# WR_LINK.net
KiCad netlist of a schematic drawn in Altium Designer
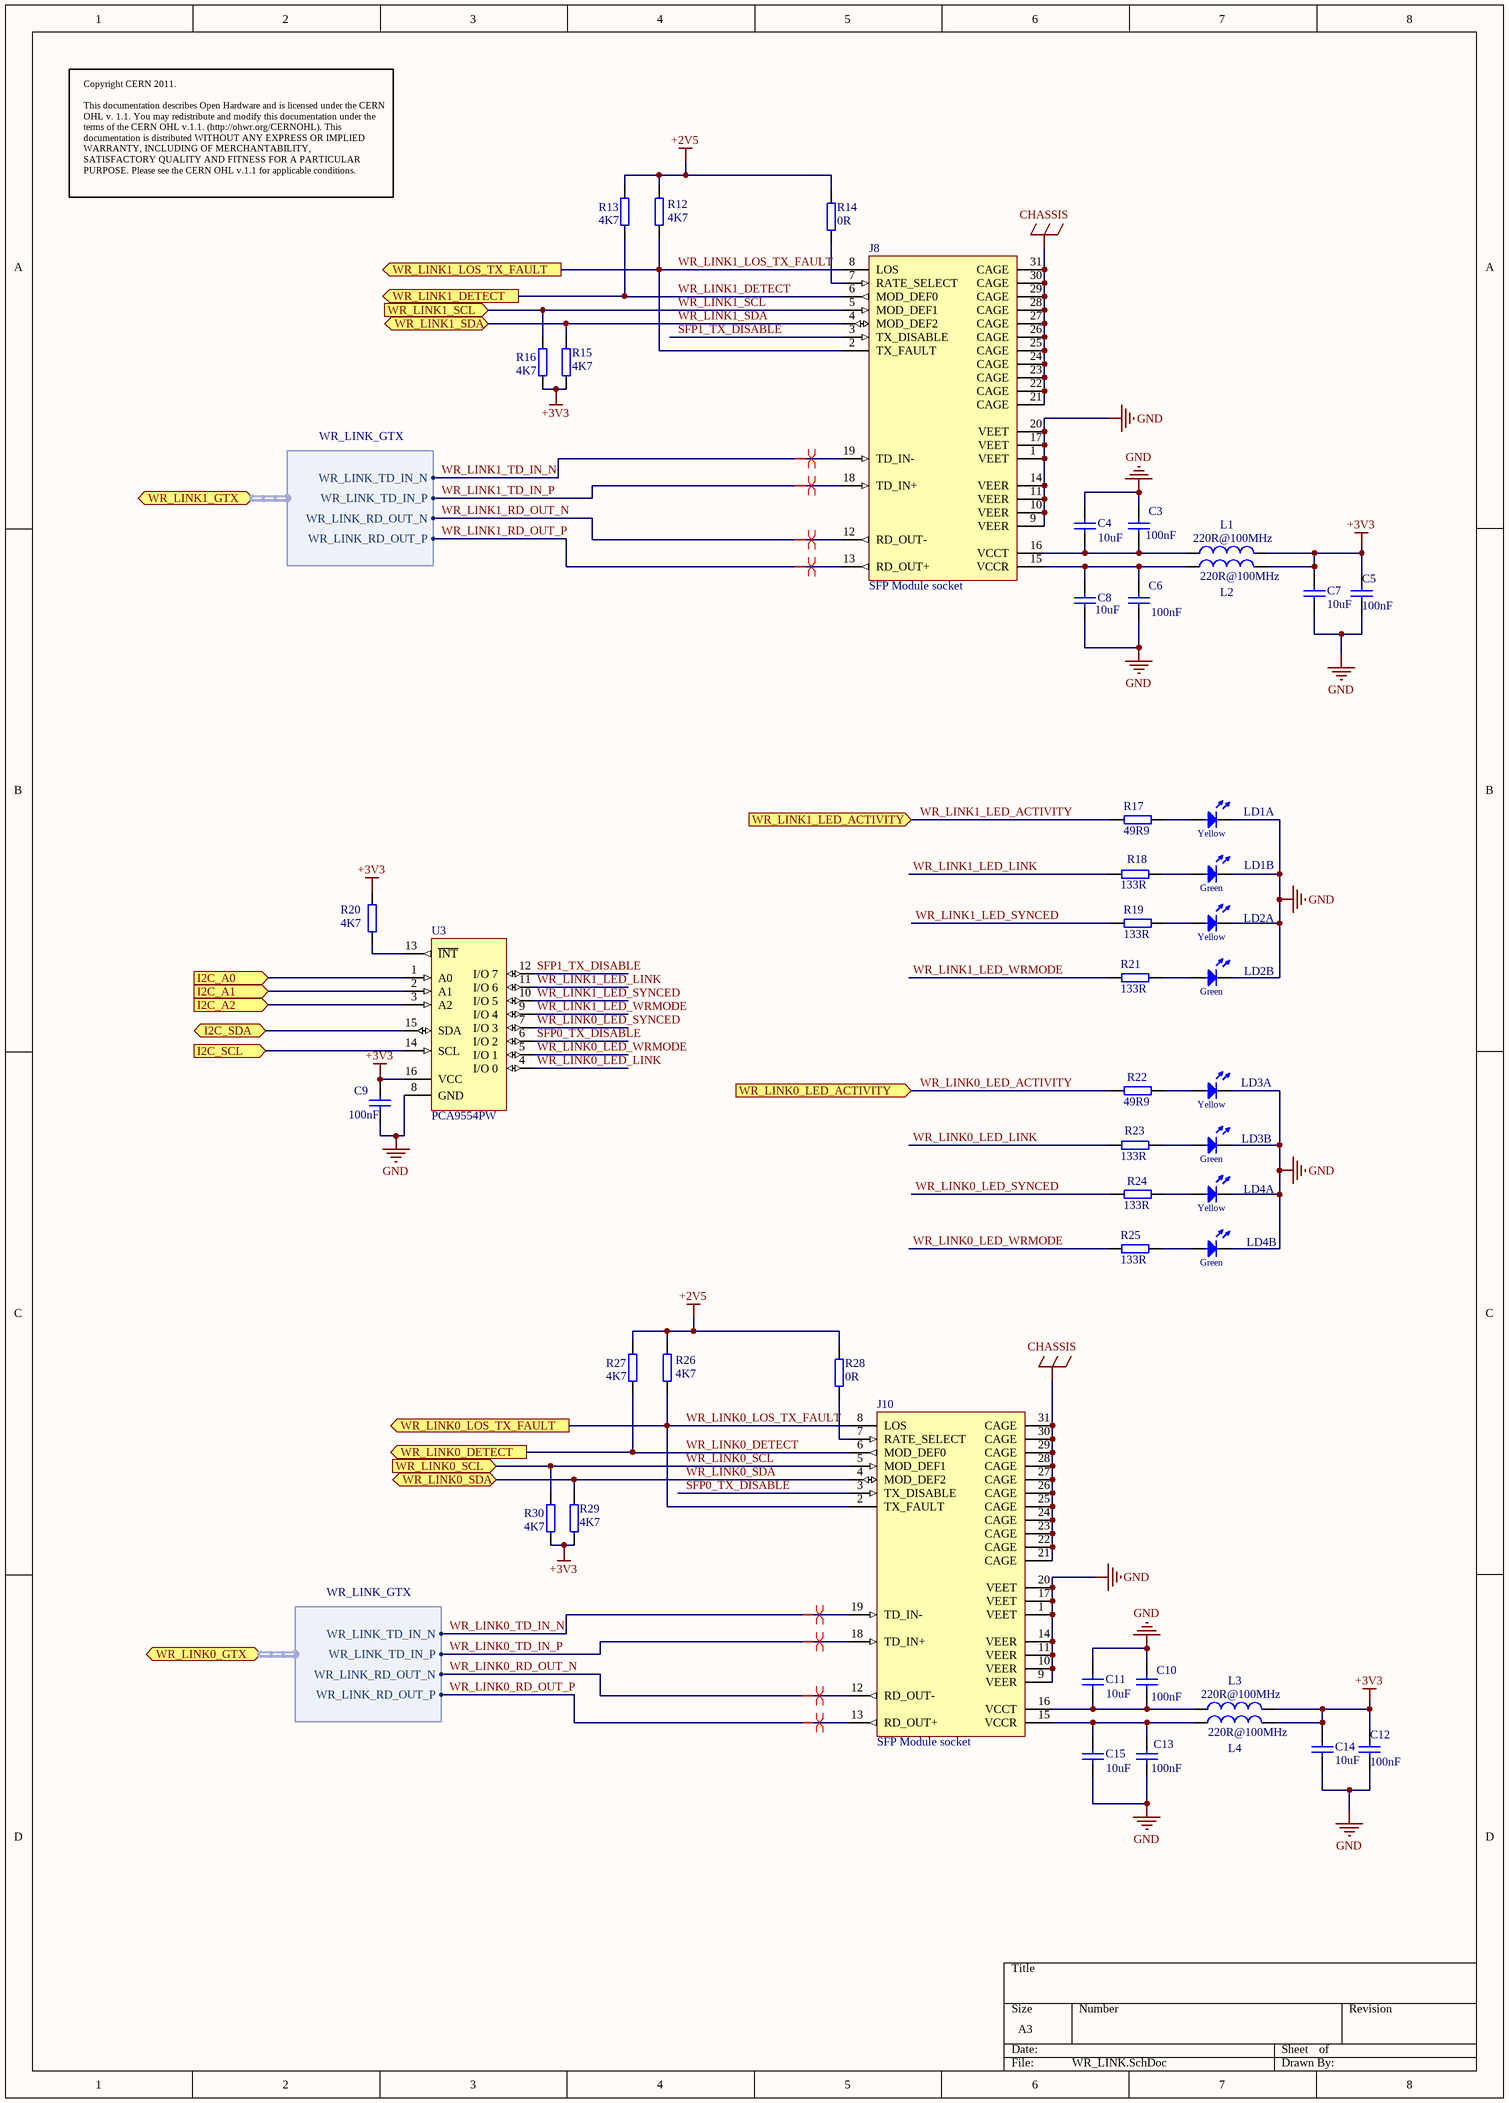
[diagram p0: WR_LINK.SchDoc]

(export (version "E")
  (design (tool "Eeschema 10.0.6"))
  (components
    (comp (ref "C3")
      (value "100nF")
      (footprint "CC1608-0603")
      (description "Capacitor")
      (fields
        (field (name "TOLERANCE") "±10%")
        (field (name "VOLTAGE") "16V")
        (field (name "PUBLISHER") "Altium Limited")
      )
      (libsource (lib "wr_switch") (part "Cap"))
    )
    (comp (ref "C4")
      (value "10uF")
      (footprint "CC2012-0805")
      (description "Capacitor")
      (fields
        (field (name "TOLERANCE") "±10%")
        (field (name "VOLTAGE") "16V")
        (field (name "PUBLISHER") "Altium Limited")
      )
      (libsource (lib "wr_switch") (part "Cap"))
    )
    (comp (ref "C5")
      (value "100nF")
      (footprint "CC1608-0603")
      (description "Capacitor")
      (fields
        (field (name "TOLERANCE") "±10%")
        (field (name "VOLTAGE") "16V")
        (field (name "PUBLISHER") "Altium Limited")
      )
      (libsource (lib "wr_switch") (part "Cap"))
    )
    (comp (ref "C6")
      (value "100nF")
      (footprint "CC1608-0603")
      (description "Capacitor")
      (fields
        (field (name "TOLERANCE") "±10%")
        (field (name "VOLTAGE") "16V")
        (field (name "PUBLISHER") "Altium Limited")
      )
      (libsource (lib "wr_switch") (part "Cap"))
    )
    (comp (ref "C7")
      (value "10uF")
      (footprint "CC1608-0603")
      (description "Capacitor")
      (fields
        (field (name "TOLERANCE") "±20%")
        (field (name "VOLTAGE") "6.3V")
        (field (name "PUBLISHER") "Altium Limited")
      )
      (libsource (lib "wr_switch") (part "Cap"))
    )
    (comp (ref "C8")
      (value "10uF")
      (footprint "CC2012-0805")
      (description "Capacitor")
      (fields
        (field (name "TOLERANCE") "±10%")
        (field (name "VOLTAGE") "16V")
        (field (name "PUBLISHER") "Altium Limited")
      )
      (libsource (lib "wr_switch") (part "Cap"))
    )
    (comp (ref "C9")
      (value "100nF")
      (footprint "CC1608-0603")
      (description "Capacitor")
      (fields
        (field (name "TOLERANCE") "±10%")
        (field (name "VOLTAGE") "16V")
        (field (name "PUBLISHER") "Altium Limited")
      )
      (libsource (lib "wr_switch") (part "Cap"))
    )
    (comp (ref "C10")
      (value "100nF")
      (footprint "CC1608-0603")
      (description "Capacitor")
      (fields
        (field (name "TOLERANCE") "±10%")
        (field (name "VOLTAGE") "16V")
        (field (name "PUBLISHER") "Altium Limited")
      )
      (libsource (lib "wr_switch") (part "Cap"))
    )
    (comp (ref "C11")
      (value "10uF")
      (footprint "CC2012-0805")
      (description "Capacitor")
      (fields
        (field (name "TOLERANCE") "±10%")
        (field (name "VOLTAGE") "16V")
        (field (name "PUBLISHER") "Altium Limited")
      )
      (libsource (lib "wr_switch") (part "Cap"))
    )
    (comp (ref "C12")
      (value "100nF")
      (footprint "CC1608-0603")
      (description "Capacitor")
      (fields
        (field (name "TOLERANCE") "±10%")
        (field (name "VOLTAGE") "16V")
        (field (name "PUBLISHER") "Altium Limited")
      )
      (libsource (lib "wr_switch") (part "Cap"))
    )
    (comp (ref "C13")
      (value "100nF")
      (footprint "CC1608-0603")
      (description "Capacitor")
      (fields
        (field (name "TOLERANCE") "±10%")
        (field (name "VOLTAGE") "16V")
        (field (name "PUBLISHER") "Altium Limited")
      )
      (libsource (lib "wr_switch") (part "Cap"))
    )
    (comp (ref "C14")
      (value "10uF")
      (footprint "CC1608-0603")
      (description "Capacitor")
      (fields
        (field (name "TOLERANCE") "±20%")
        (field (name "VOLTAGE") "6.3V")
        (field (name "PUBLISHER") "Altium Limited")
      )
      (libsource (lib "wr_switch") (part "Cap"))
    )
    (comp (ref "C15")
      (value "10uF")
      (footprint "CC2012-0805")
      (description "Capacitor")
      (fields
        (field (name "TOLERANCE") "±10%")
        (field (name "VOLTAGE") "16V")
        (field (name "PUBLISHER") "Altium Limited")
      )
      (libsource (lib "wr_switch") (part "Cap"))
    )
    (comp (ref "J8")
      (value "SFP Module socket")
      (footprint "7S_WR:SFP_SINGLE_PORT")
      (description "Socket for SFP module")
      (libsource (lib "wr_switch") (part "SFP_SOCKET_SINGLE"))
    )
    (comp (ref "J10")
      (value "SFP Module socket")
      (footprint "7S_WR:SFP_SINGLE_PORT")
      (description "Socket for SFP module")
      (libsource (lib "wr_switch") (part "SFP_SOCKET_SINGLE"))
    )
    (comp (ref "L1")
      (value "220R@100MHz Ferrite Bead")
      (footprint "0603")
      (description "ferrite bead")
      (fields (field (name "IMPEDANCE") "220R@100MHz"))
      (libsource (lib "wr_switch") (part "L_FERRITE_BEAD"))
    )
    (comp (ref "L2")
      (value "220R@100MHz Ferrite Bead")
      (footprint "0603")
      (description "ferrite bead")
      (fields (field (name "IMPEDANCE") "220R@100MHz"))
      (libsource (lib "wr_switch") (part "L_FERRITE_BEAD"))
    )
    (comp (ref "L3")
      (value "220R@100MHz Ferrite Bead")
      (footprint "0603")
      (description "ferrite bead")
      (fields (field (name "IMPEDANCE") "220R@100MHz"))
      (libsource (lib "wr_switch") (part "L_FERRITE_BEAD"))
    )
    (comp (ref "L4")
      (value "220R@100MHz Ferrite Bead")
      (footprint "0603")
      (description "ferrite bead")
      (fields (field (name "IMPEDANCE") "220R@100MHz"))
      (libsource (lib "wr_switch") (part "L_FERRITE_BEAD"))
    )
    (comp (ref "LD1")
      (value "Green/Yellow")
      (footprint "7S_WR:LED_DIALIGHT_591-3x0x-0xx")
      (description "Bi-Color LED SMD")
      (libsource (lib "wr_switch") (part "LED_DIALIGHT_591-3x0x"))
    )
    (comp (ref "LD2")
      (value "Green/Yellow")
      (footprint "7S_WR:LED_DIALIGHT_591-3x0x-0xx")
      (description "Bi-Color LED SMD")
      (libsource (lib "wr_switch") (part "LED_DIALIGHT_591-3x0x"))
    )
    (comp (ref "LD3")
      (value "Green/Yellow")
      (footprint "7S_WR:LED_DIALIGHT_591-3x0x-0xx")
      (description "Bi-Color LED SMD")
      (libsource (lib "wr_switch") (part "LED_DIALIGHT_591-3x0x"))
    )
    (comp (ref "LD4")
      (value "Green/Yellow")
      (footprint "7S_WR:LED_DIALIGHT_591-3x0x-0xx")
      (description "Bi-Color LED SMD")
      (libsource (lib "wr_switch") (part "LED_DIALIGHT_591-3x0x"))
    )
    (comp (ref "R12")
      (value "4K7")
      (footprint "0603")
      (description "SMD Resistor")
      (fields (field (name "TOLERANCE") "±1%"))
      (libsource (lib "wr_switch") (part "RES_SMD"))
    )
    (comp (ref "R13")
      (value "4K7")
      (footprint "0603")
      (description "SMD Resistor")
      (fields (field (name "TOLERANCE") "±1%"))
      (libsource (lib "wr_switch") (part "RES_SMD"))
    )
    (comp (ref "R14")
      (value "0R")
      (footprint "0603")
      (description "SMD Resistor")
      (libsource (lib "wr_switch") (part "RES_SMD"))
    )
    (comp (ref "R15")
      (value "4K7")
      (footprint "0603")
      (description "SMD Resistor")
      (fields (field (name "TOLERANCE") "±1%"))
      (libsource (lib "wr_switch") (part "RES_SMD"))
    )
    (comp (ref "R16")
      (value "4K7")
      (footprint "0603")
      (description "SMD Resistor")
      (fields (field (name "TOLERANCE") "±1%"))
      (libsource (lib "wr_switch") (part "RES_SMD"))
    )
    (comp (ref "R17")
      (value "49R9")
      (footprint "0603")
      (description "SMD Resistor")
      (fields (field (name "TOLERANCE") "±1%"))
      (libsource (lib "wr_switch") (part "RES_SMD"))
    )
    (comp (ref "R18")
      (value "133R")
      (footprint "0603")
      (description "SMD Resistor")
      (fields (field (name "TOLERANCE") "±1%"))
      (libsource (lib "wr_switch") (part "RES_SMD"))
    )
    (comp (ref "R19")
      (value "133R")
      (footprint "0603")
      (description "SMD Resistor")
      (fields (field (name "TOLERANCE") "±1%"))
      (libsource (lib "wr_switch") (part "RES_SMD"))
    )
    (comp (ref "R20")
      (value "4K7")
      (footprint "0603")
      (description "SMD Resistor")
      (fields (field (name "TOLERANCE") "±1%"))
      (libsource (lib "wr_switch") (part "RES_SMD"))
    )
    (comp (ref "R21")
      (value "133R")
      (footprint "0603")
      (description "SMD Resistor")
      (fields (field (name "TOLERANCE") "±1%"))
      (libsource (lib "wr_switch") (part "RES_SMD"))
    )
    (comp (ref "R22")
      (value "49R9")
      (footprint "0603")
      (description "SMD Resistor")
      (fields (field (name "TOLERANCE") "±1%"))
      (libsource (lib "wr_switch") (part "RES_SMD"))
    )
    (comp (ref "R23")
      (value "133R")
      (footprint "0603")
      (description "SMD Resistor")
      (fields (field (name "TOLERANCE") "±1%"))
      (libsource (lib "wr_switch") (part "RES_SMD"))
    )
    (comp (ref "R24")
      (value "133R")
      (footprint "0603")
      (description "SMD Resistor")
      (fields (field (name "TOLERANCE") "±1%"))
      (libsource (lib "wr_switch") (part "RES_SMD"))
    )
    (comp (ref "R25")
      (value "133R")
      (footprint "0603")
      (description "SMD Resistor")
      (fields (field (name "TOLERANCE") "±1%"))
      (libsource (lib "wr_switch") (part "RES_SMD"))
    )
    (comp (ref "R26")
      (value "4K7")
      (footprint "0603")
      (description "SMD Resistor")
      (fields (field (name "TOLERANCE") "±1%"))
      (libsource (lib "wr_switch") (part "RES_SMD"))
    )
    (comp (ref "R27")
      (value "4K7")
      (footprint "0603")
      (description "SMD Resistor")
      (fields (field (name "TOLERANCE") "±1%"))
      (libsource (lib "wr_switch") (part "RES_SMD"))
    )
    (comp (ref "R28")
      (value "0R")
      (footprint "0603")
      (description "SMD Resistor")
      (libsource (lib "wr_switch") (part "RES_SMD"))
    )
    (comp (ref "R29")
      (value "4K7")
      (footprint "0603")
      (description "SMD Resistor")
      (fields (field (name "TOLERANCE") "±1%"))
      (libsource (lib "wr_switch") (part "RES_SMD"))
    )
    (comp (ref "R30")
      (value "4K7")
      (footprint "0603")
      (description "SMD Resistor")
      (fields (field (name "TOLERANCE") "±1%"))
      (libsource (lib "wr_switch") (part "RES_SMD"))
    )
    (comp (ref "U3")
      (value "PCA9554PW")
      (footprint "SOP65P640X120-16N")
      (description "8-bit I2C-bus SMBus I/O port with interrupt")
      (libsource (lib "wr_switch") (part "PCA9554D"))
    )
  )
  (nets
    (net (code "2") (name "+2V5") (class "Default")
      (node (ref "R12") (pin "2") (pinfunction "2_2") (pintype "passive"))
      (node (ref "R13") (pin "2") (pinfunction "2_2") (pintype "passive"))
      (node (ref "R14") (pin "1") (pinfunction "1_1") (pintype "passive"))
      (node (ref "R26") (pin "2") (pinfunction "2_2") (pintype "passive"))
      (node (ref "R27") (pin "2") (pinfunction "2_2") (pintype "passive"))
      (node (ref "R28") (pin "1") (pinfunction "1_1") (pintype "passive"))
    )
    (net (code "3") (name "+3V3") (class "Default")
      (node (ref "C12") (pin "1") (pinfunction "1_1") (pintype "passive"))
      (node (ref "C14") (pin "1") (pinfunction "1_1") (pintype "passive"))
      (node (ref "C5") (pin "1") (pinfunction "1_1") (pintype "passive"))
      (node (ref "C7") (pin "1") (pinfunction "1_1") (pintype "passive"))
      (node (ref "C9") (pin "1") (pinfunction "1_1") (pintype "passive"))
      (node (ref "L1") (pin "2") (pinfunction "2_2") (pintype "passive"))
      (node (ref "L2") (pin "2") (pinfunction "2_2") (pintype "passive"))
      (node (ref "L3") (pin "2") (pinfunction "2_2") (pintype "passive"))
      (node (ref "L4") (pin "2") (pinfunction "2_2") (pintype "passive"))
      (node (ref "R15") (pin "2") (pinfunction "2_2") (pintype "passive"))
      (node (ref "R16") (pin "2") (pinfunction "2_2") (pintype "passive"))
      (node (ref "R20") (pin "2") (pinfunction "2_2") (pintype "passive"))
      (node (ref "R29") (pin "2") (pinfunction "2_2") (pintype "passive"))
      (node (ref "R30") (pin "2") (pinfunction "2_2") (pintype "passive"))
      (node (ref "U3") (pin "16") (pinfunction "VCC_16") (pintype "power_in"))
    )
    (net (code "4") (name "/I2C_A0") (class "Default")
      (node (ref "U3") (pin "1") (pinfunction "A0_1") (pintype "input"))
    )
    (net (code "5") (name "/I2C_A1") (class "Default")
      (node (ref "U3") (pin "2") (pinfunction "A1_2") (pintype "input"))
    )
    (net (code "6") (name "/I2C_A2") (class "Default")
      (node (ref "U3") (pin "3") (pinfunction "A2_3") (pintype "input"))
    )
    (net (code "7") (name "/I2C_SCL") (class "Default")
      (node (ref "U3") (pin "14") (pinfunction "SCL_14") (pintype "input"))
    )
    (net (code "8") (name "/I2C_SDA") (class "Default")
      (node (ref "U3") (pin "15") (pinfunction "SDA_15") (pintype "bidirectional"))
    )
    (net (code "9") (name "/SFP0_TX_DISABLE") (class "Default")
      (node (ref "J10") (pin "3") (pinfunction "TX_DISABLE_3") (pintype "input"))
      (node (ref "U3") (pin "6") (pinfunction "I/O_2_6") (pintype "bidirectional"))
    )
    (net (code "10") (name "/SFP1_TX_DISABLE") (class "Default")
      (node (ref "J8") (pin "3") (pinfunction "TX_DISABLE_3") (pintype "input"))
      (node (ref "U3") (pin "12") (pinfunction "I/O_7_12") (pintype "bidirectional"))
    )
    (net (code "11") (name "/WR_LINK0_DETECT") (class "Default")
      (node (ref "J10") (pin "6") (pinfunction "MOD_DEF0_6") (pintype "output"))
      (node (ref "R27") (pin "1") (pinfunction "1_1") (pintype "passive"))
    )
    (net (code "12") (name "/WR_LINK0_LED_ACTIVITY") (class "Default")
      (node (ref "R22") (pin "1") (pinfunction "1_1") (pintype "passive"))
    )
    (net (code "13") (name "/WR_LINK0_LED_LINK") (class "Default")
      (node (ref "R23") (pin "1") (pinfunction "1_1") (pintype "passive"))
      (node (ref "U3") (pin "4") (pinfunction "I/O_0_4") (pintype "bidirectional"))
    )
    (net (code "14") (name "/WR_LINK0_LED_SYNCED") (class "Default")
      (node (ref "R24") (pin "1") (pinfunction "1_1") (pintype "passive"))
      (node (ref "U3") (pin "7") (pinfunction "I/O_3_7") (pintype "bidirectional"))
    )
    (net (code "15") (name "/WR_LINK0_LED_WRMODE") (class "Default")
      (node (ref "R25") (pin "1") (pinfunction "1_1") (pintype "passive"))
      (node (ref "U3") (pin "5") (pinfunction "I/O_1_5") (pintype "bidirectional"))
    )
    (net (code "16") (name "/WR_LINK0_LOS_TX_FAULT") (class "Default")
      (node (ref "J10") (pin "2") (pinfunction "TX_FAULT_2") (pintype "open_collector"))
      (node (ref "J10") (pin "8") (pinfunction "LOS_8") (pintype "open_collector"))
      (node (ref "R26") (pin "1") (pinfunction "1_1") (pintype "passive"))
    )
    (net (code "17") (name "/WR_LINK0_RD_OUT_N") (class "Default")
      (node (ref "J10") (pin "12") (pinfunction "RD_OUT-_12") (pintype "output"))
    )
    (net (code "18") (name "/WR_LINK0_RD_OUT_P") (class "Default")
      (node (ref "J10") (pin "13") (pinfunction "RD_OUT+_13") (pintype "output"))
    )
    (net (code "19") (name "/WR_LINK0_SCL") (class "Default")
      (node (ref "J10") (pin "5") (pinfunction "MOD_DEF1_5") (pintype "input"))
      (node (ref "R30") (pin "1") (pinfunction "1_1") (pintype "passive"))
    )
    (net (code "20") (name "/WR_LINK0_SDA") (class "Default")
      (node (ref "J10") (pin "4") (pinfunction "MOD_DEF2_4") (pintype "bidirectional"))
      (node (ref "R29") (pin "1") (pinfunction "1_1") (pintype "passive"))
    )
    (net (code "21") (name "/WR_LINK0_TD_IN_N") (class "Default")
      (node (ref "J10") (pin "19") (pinfunction "TD_IN-_19") (pintype "input"))
    )
    (net (code "22") (name "/WR_LINK0_TD_IN_P") (class "Default")
      (node (ref "J10") (pin "18") (pinfunction "TD_IN+_18") (pintype "input"))
    )
    (net (code "23") (name "/WR_LINK1_DETECT") (class "Default")
      (node (ref "J8") (pin "6") (pinfunction "MOD_DEF0_6") (pintype "output"))
      (node (ref "R13") (pin "1") (pinfunction "1_1") (pintype "passive"))
    )
    (net (code "24") (name "/WR_LINK1_LED_ACTIVITY") (class "Default")
      (node (ref "R17") (pin "1") (pinfunction "1_1") (pintype "passive"))
    )
    (net (code "25") (name "/WR_LINK1_LED_LINK") (class "Default")
      (node (ref "R18") (pin "1") (pinfunction "1_1") (pintype "passive"))
      (node (ref "U3") (pin "11") (pinfunction "I/O_6_11") (pintype "bidirectional"))
    )
    (net (code "26") (name "/WR_LINK1_LED_SYNCED") (class "Default")
      (node (ref "R19") (pin "1") (pinfunction "1_1") (pintype "passive"))
      (node (ref "U3") (pin "10") (pinfunction "I/O_5_10") (pintype "bidirectional"))
    )
    (net (code "27") (name "/WR_LINK1_LED_WRMODE") (class "Default")
      (node (ref "R21") (pin "1") (pinfunction "1_1") (pintype "passive"))
      (node (ref "U3") (pin "9") (pinfunction "I/O_4_9") (pintype "bidirectional"))
    )
    (net (code "28") (name "/WR_LINK1_LOS_TX_FAULT") (class "Default")
      (node (ref "J8") (pin "2") (pinfunction "TX_FAULT_2") (pintype "open_collector"))
      (node (ref "J8") (pin "8") (pinfunction "LOS_8") (pintype "open_collector"))
      (node (ref "R12") (pin "1") (pinfunction "1_1") (pintype "passive"))
    )
    (net (code "29") (name "/WR_LINK1_RD_OUT_N") (class "Default")
      (node (ref "J8") (pin "12") (pinfunction "RD_OUT-_12") (pintype "output"))
    )
    (net (code "30") (name "/WR_LINK1_RD_OUT_P") (class "Default")
      (node (ref "J8") (pin "13") (pinfunction "RD_OUT+_13") (pintype "output"))
    )
    (net (code "31") (name "/WR_LINK1_SCL") (class "Default")
      (node (ref "J8") (pin "5") (pinfunction "MOD_DEF1_5") (pintype "input"))
      (node (ref "R16") (pin "1") (pinfunction "1_1") (pintype "passive"))
    )
    (net (code "32") (name "/WR_LINK1_SDA") (class "Default")
      (node (ref "J8") (pin "4") (pinfunction "MOD_DEF2_4") (pintype "bidirectional"))
      (node (ref "R15") (pin "1") (pinfunction "1_1") (pintype "passive"))
    )
    (net (code "33") (name "/WR_LINK1_TD_IN_N") (class "Default")
      (node (ref "J8") (pin "19") (pinfunction "TD_IN-_19") (pintype "input"))
    )
    (net (code "34") (name "/WR_LINK1_TD_IN_P") (class "Default")
      (node (ref "J8") (pin "18") (pinfunction "TD_IN+_18") (pintype "input"))
    )
    (net (code "36") (name "CHASSIS") (class "Default")
      (node (ref "J10") (pin "21") (pinfunction "CAGE_21") (pintype "power_in"))
      (node (ref "J10") (pin "22") (pinfunction "CAGE_22") (pintype "power_in"))
      (node (ref "J10") (pin "23") (pinfunction "CAGE_23") (pintype "power_in"))
      (node (ref "J10") (pin "24") (pinfunction "CAGE_24") (pintype "power_in"))
      (node (ref "J10") (pin "25") (pinfunction "CAGE_25") (pintype "power_in"))
      (node (ref "J10") (pin "26") (pinfunction "CAGE_26") (pintype "power_in"))
      (node (ref "J10") (pin "27") (pinfunction "CAGE_27") (pintype "power_in"))
      (node (ref "J10") (pin "28") (pinfunction "CAGE_28") (pintype "power_in"))
      (node (ref "J10") (pin "29") (pinfunction "CAGE_29") (pintype "power_in"))
      (node (ref "J10") (pin "30") (pinfunction "CAGE_30") (pintype "power_in"))
      (node (ref "J10") (pin "31") (pinfunction "CAGE_31") (pintype "power_in"))
      (node (ref "J8") (pin "21") (pinfunction "CAGE_21") (pintype "power_in"))
      (node (ref "J8") (pin "22") (pinfunction "CAGE_22") (pintype "power_in"))
      (node (ref "J8") (pin "23") (pinfunction "CAGE_23") (pintype "power_in"))
      (node (ref "J8") (pin "24") (pinfunction "CAGE_24") (pintype "power_in"))
      (node (ref "J8") (pin "25") (pinfunction "CAGE_25") (pintype "power_in"))
      (node (ref "J8") (pin "26") (pinfunction "CAGE_26") (pintype "power_in"))
      (node (ref "J8") (pin "27") (pinfunction "CAGE_27") (pintype "power_in"))
      (node (ref "J8") (pin "28") (pinfunction "CAGE_28") (pintype "power_in"))
      (node (ref "J8") (pin "29") (pinfunction "CAGE_29") (pintype "power_in"))
      (node (ref "J8") (pin "30") (pinfunction "CAGE_30") (pintype "power_in"))
      (node (ref "J8") (pin "31") (pinfunction "CAGE_31") (pintype "power_in"))
    )
    (net (code "37") (name "GND") (class "Default")
      (node (ref "C10") (pin "1") (pinfunction "1_1") (pintype "passive"))
      (node (ref "C11") (pin "2") (pinfunction "2_2") (pintype "passive"))
      (node (ref "C12") (pin "2") (pinfunction "2_2") (pintype "passive"))
      (node (ref "C13") (pin "2") (pinfunction "2_2") (pintype "passive"))
      (node (ref "C14") (pin "2") (pinfunction "2_2") (pintype "passive"))
      (node (ref "C15") (pin "1") (pinfunction "1_1") (pintype "passive"))
      (node (ref "C3") (pin "1") (pinfunction "1_1") (pintype "passive"))
      (node (ref "C4") (pin "2") (pinfunction "2_2") (pintype "passive"))
      (node (ref "C5") (pin "2") (pinfunction "2_2") (pintype "passive"))
      (node (ref "C6") (pin "2") (pinfunction "2_2") (pintype "passive"))
      (node (ref "C7") (pin "2") (pinfunction "2_2") (pintype "passive"))
      (node (ref "C8") (pin "1") (pinfunction "1_1") (pintype "passive"))
      (node (ref "C9") (pin "2") (pinfunction "2_2") (pintype "passive"))
      (node (ref "J10") (pin "1") (pinfunction "VEET_1") (pintype "power_in"))
      (node (ref "J10") (pin "10") (pinfunction "VEER_10") (pintype "power_in"))
      (node (ref "J10") (pin "11") (pinfunction "VEER_11") (pintype "power_in"))
      (node (ref "J10") (pin "14") (pinfunction "VEER_14") (pintype "power_in"))
      (node (ref "J10") (pin "17") (pinfunction "VEET_17") (pintype "power_in"))
      (node (ref "J10") (pin "20") (pinfunction "VEET_20") (pintype "power_in"))
      (node (ref "J10") (pin "9") (pinfunction "VEER_9") (pintype "power_in"))
      (node (ref "J8") (pin "1") (pinfunction "VEET_1") (pintype "power_in"))
      (node (ref "J8") (pin "10") (pinfunction "VEER_10") (pintype "power_in"))
      (node (ref "J8") (pin "11") (pinfunction "VEER_11") (pintype "power_in"))
      (node (ref "J8") (pin "14") (pinfunction "VEER_14") (pintype "power_in"))
      (node (ref "J8") (pin "17") (pinfunction "VEET_17") (pintype "power_in"))
      (node (ref "J8") (pin "20") (pinfunction "VEET_20") (pintype "power_in"))
      (node (ref "J8") (pin "9") (pinfunction "VEER_9") (pintype "power_in"))
      (node (ref "LD1") (pin "1") (pinfunction "C_1") (pintype "passive"))
      (node (ref "LD1") (pin "4") (pinfunction "C_4") (pintype "passive"))
      (node (ref "LD2") (pin "1") (pinfunction "C_1") (pintype "passive"))
      (node (ref "LD2") (pin "4") (pinfunction "C_4") (pintype "passive"))
      (node (ref "LD3") (pin "1") (pinfunction "C_1") (pintype "passive"))
      (node (ref "LD3") (pin "4") (pinfunction "C_4") (pintype "passive"))
      (node (ref "LD4") (pin "1") (pinfunction "C_1") (pintype "passive"))
      (node (ref "LD4") (pin "4") (pinfunction "C_4") (pintype "passive"))
      (node (ref "U3") (pin "8") (pinfunction "GND_8") (pintype "power_in"))
    )
    (net (code "38") (name "Net-(J8-RATE_SELECT)") (class "Default")
      (node (ref "J8") (pin "7") (pinfunction "RATE_SELECT_7") (pintype "input"))
      (node (ref "R14") (pin "2") (pinfunction "2_2") (pintype "passive"))
    )
    (net (code "39") (name "Net-(J8-VCCR)") (class "Default")
      (node (ref "C6") (pin "1") (pinfunction "1_1") (pintype "passive"))
      (node (ref "C8") (pin "2") (pinfunction "2_2") (pintype "passive"))
      (node (ref "J8") (pin "15") (pinfunction "VCCR_15") (pintype "power_in"))
      (node (ref "L2") (pin "1") (pinfunction "1_1") (pintype "passive"))
    )
    (net (code "40") (name "Net-(J8-VCCT)") (class "Default")
      (node (ref "C3") (pin "2") (pinfunction "2_2") (pintype "passive"))
      (node (ref "C4") (pin "1") (pinfunction "1_1") (pintype "passive"))
      (node (ref "J8") (pin "16") (pinfunction "VCCT_16") (pintype "power_in"))
      (node (ref "L1") (pin "1") (pinfunction "1_1") (pintype "passive"))
    )
    (net (code "41") (name "Net-(J10-RATE_SELECT)") (class "Default")
      (node (ref "J10") (pin "7") (pinfunction "RATE_SELECT_7") (pintype "input"))
      (node (ref "R28") (pin "2") (pinfunction "2_2") (pintype "passive"))
    )
    (net (code "42") (name "Net-(J10-VCCR)") (class "Default")
      (node (ref "C13") (pin "1") (pinfunction "1_1") (pintype "passive"))
      (node (ref "C15") (pin "2") (pinfunction "2_2") (pintype "passive"))
      (node (ref "J10") (pin "15") (pinfunction "VCCR_15") (pintype "power_in"))
      (node (ref "L4") (pin "1") (pinfunction "1_1") (pintype "passive"))
    )
    (net (code "43") (name "Net-(J10-VCCT)") (class "Default")
      (node (ref "C10") (pin "2") (pinfunction "2_2") (pintype "passive"))
      (node (ref "C11") (pin "1") (pinfunction "1_1") (pintype "passive"))
      (node (ref "J10") (pin "16") (pinfunction "VCCT_16") (pintype "power_in"))
      (node (ref "L3") (pin "1") (pinfunction "1_1") (pintype "passive"))
    )
    (net (code "44") (name "Net-(LD1A-A)") (class "Default")
      (node (ref "LD1") (pin "2") (pinfunction "A_2") (pintype "passive"))
      (node (ref "R17") (pin "2") (pinfunction "2_2") (pintype "passive"))
    )
    (net (code "45") (name "Net-(LD1B-A)") (class "Default")
      (node (ref "LD1") (pin "3") (pinfunction "A_3") (pintype "passive"))
      (node (ref "R18") (pin "2") (pinfunction "2_2") (pintype "passive"))
    )
    (net (code "46") (name "Net-(LD2A-A)") (class "Default")
      (node (ref "LD2") (pin "2") (pinfunction "A_2") (pintype "passive"))
      (node (ref "R19") (pin "2") (pinfunction "2_2") (pintype "passive"))
    )
    (net (code "47") (name "Net-(LD2B-A)") (class "Default")
      (node (ref "LD2") (pin "3") (pinfunction "A_3") (pintype "passive"))
      (node (ref "R21") (pin "2") (pinfunction "2_2") (pintype "passive"))
    )
    (net (code "48") (name "Net-(LD3A-A)") (class "Default")
      (node (ref "LD3") (pin "2") (pinfunction "A_2") (pintype "passive"))
      (node (ref "R22") (pin "2") (pinfunction "2_2") (pintype "passive"))
    )
    (net (code "49") (name "Net-(LD3B-A)") (class "Default")
      (node (ref "LD3") (pin "3") (pinfunction "A_3") (pintype "passive"))
      (node (ref "R23") (pin "2") (pinfunction "2_2") (pintype "passive"))
    )
    (net (code "50") (name "Net-(LD4A-A)") (class "Default")
      (node (ref "LD4") (pin "2") (pinfunction "A_2") (pintype "passive"))
      (node (ref "R24") (pin "2") (pinfunction "2_2") (pintype "passive"))
    )
    (net (code "51") (name "Net-(LD4B-A)") (class "Default")
      (node (ref "LD4") (pin "3") (pinfunction "A_3") (pintype "passive"))
      (node (ref "R25") (pin "2") (pinfunction "2_2") (pintype "passive"))
    )
    (net (code "52") (name "Net-(U3-~{INT})") (class "Default")
      (node (ref "R20") (pin "1") (pinfunction "1_1") (pintype "passive"))
      (node (ref "U3") (pin "13") (pinfunction "~{INT}_13") (pintype "output"))
    )
  )
)
